# 4_Sensors.net
KiCad netlist of a schematic drawn in Altium Designer
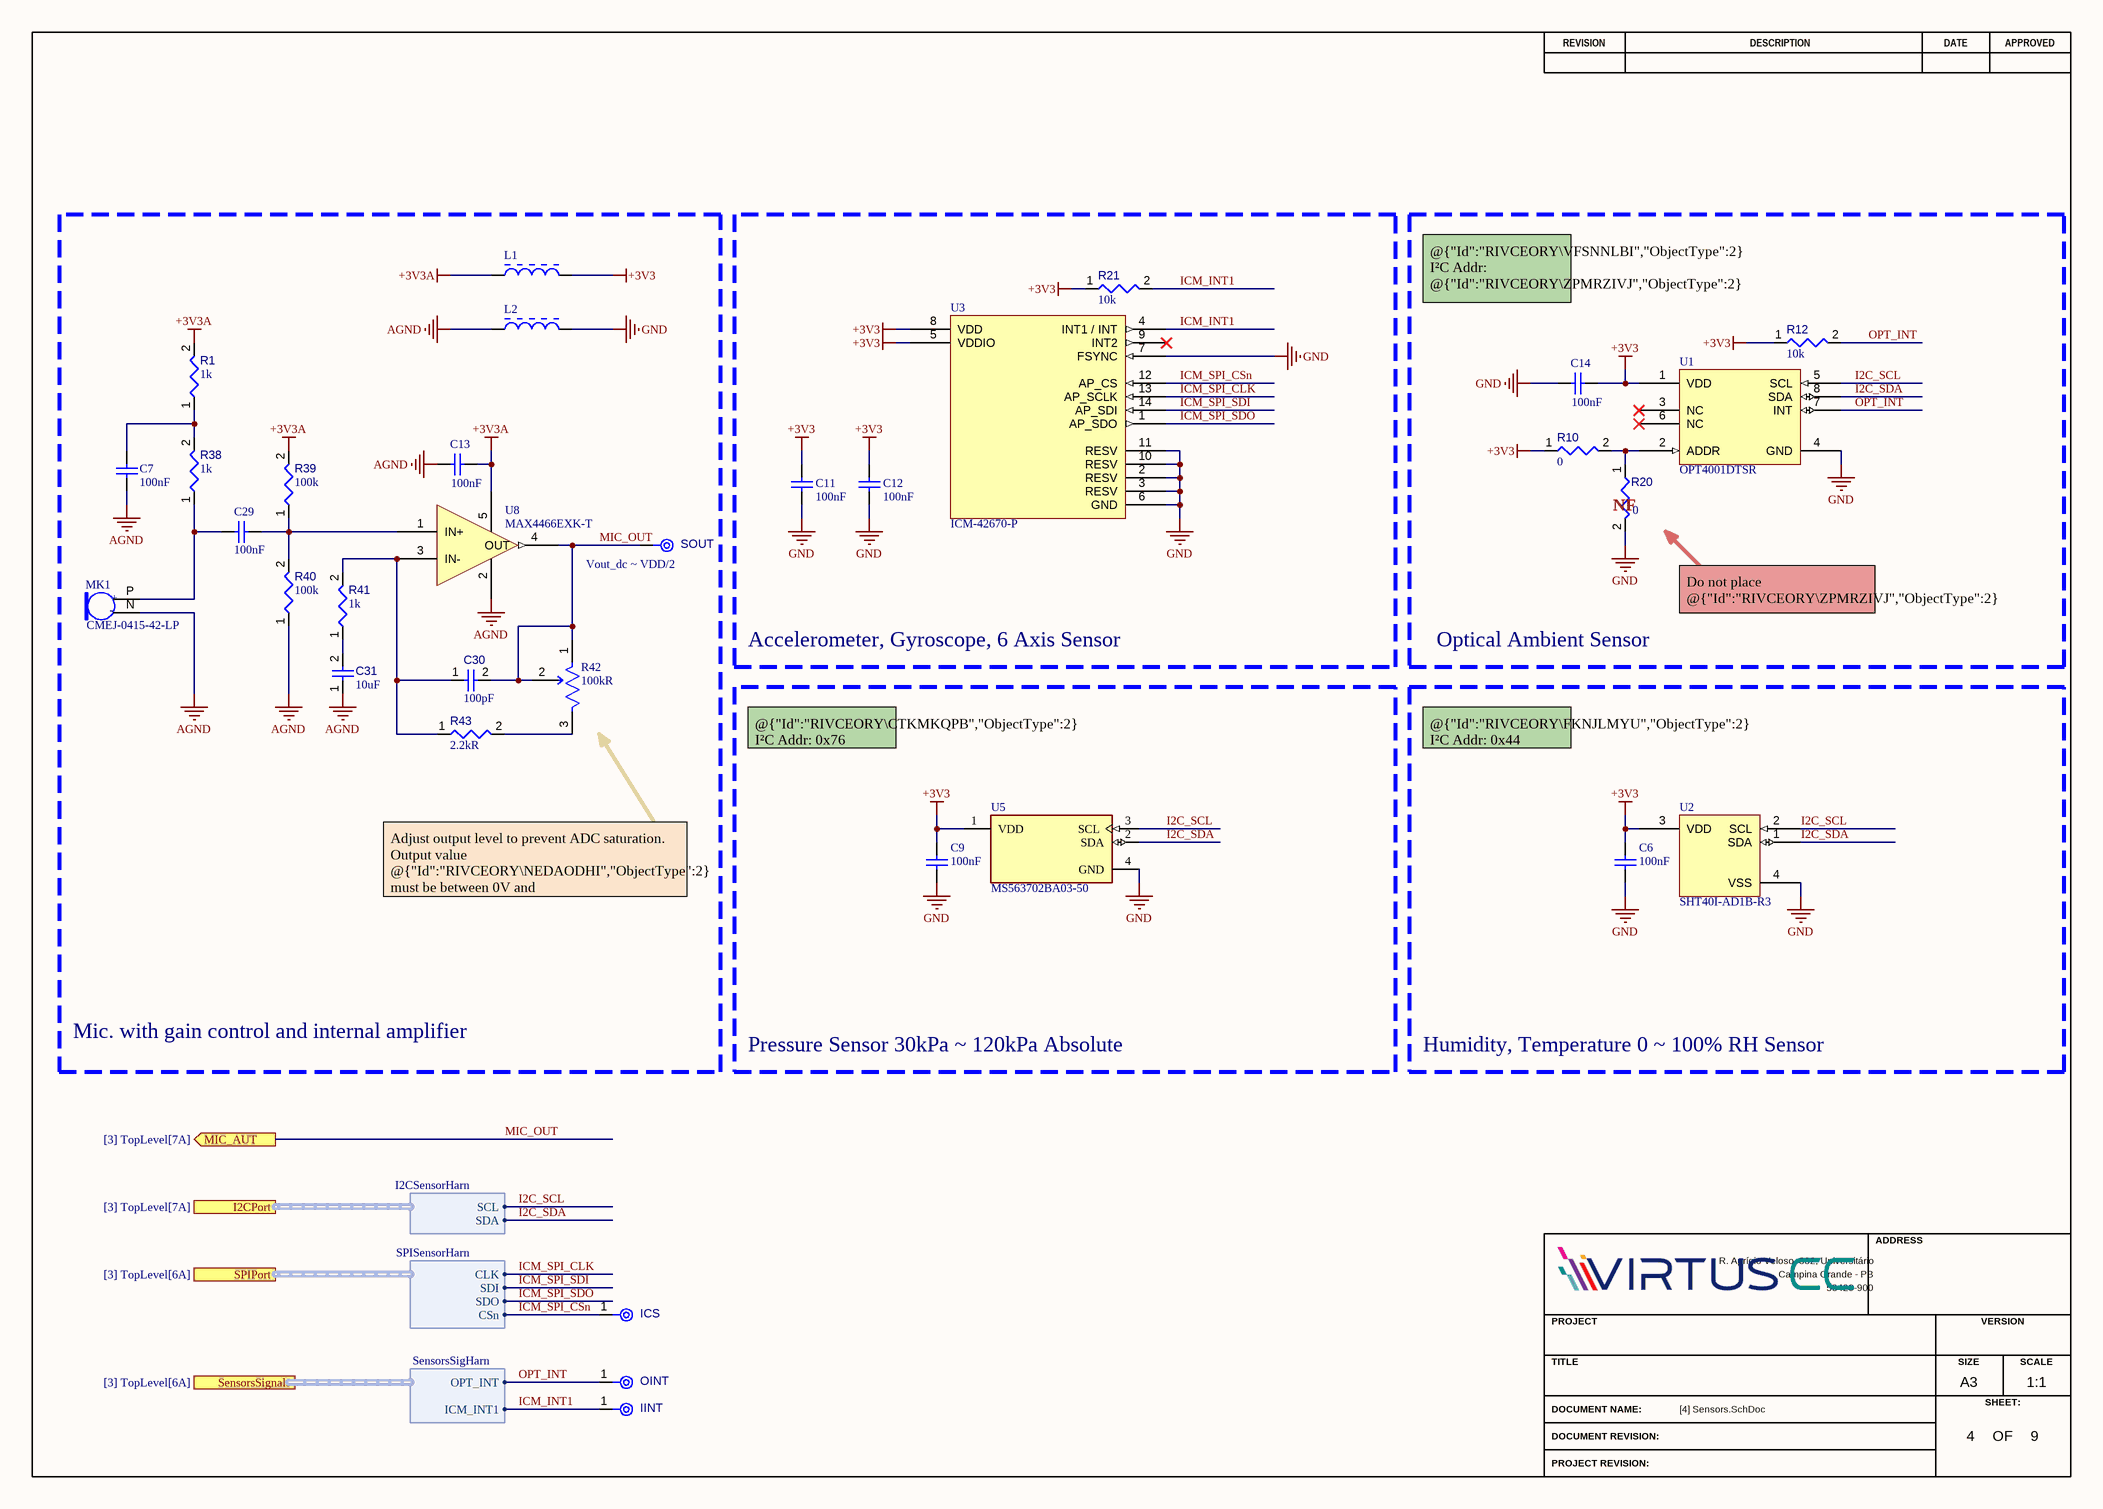
[diagram p0: [4] Sensors.SchDoc]

(export (version "E")
  (design (tool "Eeschema 10.0.6"))
  (components
    (comp (ref "C6")
      (value "100nF")
      (footprint "CAPC0603(1608)100_L")
      (description "Multilayer Ceramic Capacitor, 0.1 uF, 16 V, ± 20%, X7R, 0603 [1608 Metric]")
      (fields (field (name "TOLERANCE") "20%") (field (name "Comment") "VJ0603Y104MXJCW1BC"))
      (libsource (lib "UFCG - Universidade Federal de Campina Grande") (part "CAP"))
    )
    (comp (ref "C7")
      (value "100nF")
      (footprint "CAPC0603(1608)100_L")
      (description "Multilayer Ceramic Capacitor, 0.1 uF, 16 V, ± 20%, X7R, 0603 [1608 Metric]")
      (fields (field (name "TOLERANCE") "20%") (field (name "Comment") "VJ0603Y104MXJCW1BC"))
      (libsource (lib "UFCG - Universidade Federal de Campina Grande") (part "CAP"))
    )
    (comp (ref "C9")
      (value "100nF")
      (footprint "CAPC0603(1608)100_L")
      (description "Multilayer Ceramic Capacitor, 0.1 uF, 16 V, ± 20%, X7R, 0603 [1608 Metric]")
      (fields (field (name "TOLERANCE") "20%") (field (name "Comment") "VJ0603Y104MXJCW1BC"))
      (libsource (lib "UFCG - Universidade Federal de Campina Grande") (part "CAP"))
    )
    (comp (ref "C11")
      (value "100nF")
      (footprint "CAPC0603(1608)100_L")
      (description "Multilayer Ceramic Capacitor, 0.1 uF, 16 V, ± 20%, X7R, 0603 [1608 Metric]")
      (fields (field (name "TOLERANCE") "20%") (field (name "Comment") "VJ0603Y104MXJCW1BC"))
      (libsource (lib "UFCG - Universidade Federal de Campina Grande") (part "CAP"))
    )
    (comp (ref "C12")
      (value "100nF")
      (footprint "CAPC0603(1608)100_L")
      (description "Multilayer Ceramic Capacitor, 0.1 uF, 16 V, ± 20%, X7R, 0603 [1608 Metric]")
      (fields (field (name "TOLERANCE") "20%") (field (name "Comment") "VJ0603Y104MXJCW1BC"))
      (libsource (lib "UFCG - Universidade Federal de Campina Grande") (part "CAP"))
    )
    (comp (ref "C13")
      (value "100nF")
      (footprint "CAPC0603(1608)100_L")
      (description "Multilayer Ceramic Capacitor, 0.1 uF, 16 V, ± 20%, X7R, 0603 [1608 Metric]")
      (fields (field (name "TOLERANCE") "20%") (field (name "Comment") "VJ0603Y104MXJCW1BC"))
      (libsource (lib "UFCG - Universidade Federal de Campina Grande") (part "CAP"))
    )
    (comp (ref "C14")
      (value "100nF")
      (footprint "CAPC0603(1608)100_L")
      (description "Multilayer Ceramic Capacitor, 0.1 uF, 16 V, ± 20%, X7R, 0603 [1608 Metric]")
      (fields (field (name "TOLERANCE") "20%") (field (name "Comment") "VJ0603Y104MXJCW1BC"))
      (libsource (lib "UFCG - Universidade Federal de Campina Grande") (part "CAP"))
    )
    (comp (ref "C29")
      (value "100nF")
      (footprint "CAPC0603(1608)100_L")
      (description "Multilayer Ceramic Capacitor, 0.1 uF, 16 V, ± 20%, X7R, 0603 [1608 Metric]")
      (fields (field (name "TOLERANCE") "20%") (field (name "Comment") "VJ0603Y104MXJCW1BC"))
      (libsource (lib "UFCG - Universidade Federal de Campina Grande") (part "CAP"))
    )
    (comp (ref "C30")
      (value "100pF")
      (footprint "CAPC0603(1608)100_L")
      (description "Multilayer Ceramic Capacitor, 100 pF, 50 V, ï¿½ 10%, C0G (NP0), 0603 [1608 Metric]")
      (fields (field (name "TOLERANCE") "10%") (field (name "Comment") "C0603C101K5GACTU"))
      (libsource (lib "UFCG - Universidade Federal de Campina Grande") (part "CAP-NP-2"))
    )
    (comp (ref "C31")
      (value "10uF")
      (footprint "CAPC0603(1608)100_L")
      (description "Multilayer Ceramic Capacitor, 10 uF, 6.3 V, ± 20%, X5R, 0603 [1608 Metric]")
      (fields (field (name "TOLERANCE") "20%") (field (name "Comment") "GRM188R60J106ME47D"))
      (libsource (lib "UFCG - Universidade Federal de Campina Grande") (part "CAP-NP-2"))
    )
    (comp (ref "ICS")
      (value "TPAD6R")
      (footprint "TP06R")
      (description "0.6mm round")
      (libsource (lib "") (part "CMP-001-0001-4_1"))
    )
    (comp (ref "IINT")
      (value "TPAD6R")
      (footprint "TP06R")
      (description "0.6mm round")
      (libsource (lib "") (part "CMP-001-0001-4_1"))
    )
    (comp (ref "L1")
      (value "BLM21PG331SN1D")
      (footprint "INDC2013X105X50ML20T20")
      (fields (field (name "TOLERANCE") "25%") (field (name "MANUFACTURER") "Murata"))
      (libsource (lib "UFCG - Universidade Federal de Campina Grande") (part "IND-FB-2"))
    )
    (comp (ref "L2")
      (value "BLM21PG331SN1D")
      (footprint "INDC2013X105X50ML20T20")
      (fields (field (name "TOLERANCE") "25%") (field (name "MANUFACTURER") "Murata"))
      (libsource (lib "UFCG - Universidade Federal de Campina Grande") (part "IND-FB-2"))
    )
    (comp (ref "MK1")
      (value "CMEJ-0415-42-LP")
      (footprint "MIC_CMEJ-0415-42-LP")
      (description "4.0 mm, Omnidirectional, PCB Mount, 2.0 Vdc, Elecret Condenser Microphone")
      (fields (field (name "MF") "{'manufacturer': u'CUI'}"))
      (libsource (lib "UFCG - Universidade Federal de Campina Grande") (part "CMEJ-0415-42-LP"))
    )
    (comp (ref "OINT")
      (value "TPAD6R")
      (footprint "TP06R")
      (description "0.6mm round")
      (libsource (lib "") (part "CMP-001-0001-4_1"))
    )
    (comp (ref "R1")
      (value "1k")
      (footprint "RESC0603(1608)_L")
      (description "Chip Resistor, 1 KOhm, +/-1%, 0.1 W, -55 to 155 degC, 0603 (1608 Metric)")
      (fields (field (name "POWER") "100mW") (field (name "TOLERANCE") "1%"))
      (libsource (lib "UFCG - Universidade Federal de Campina Grande") (part "RES-2"))
    )
    (comp (ref "R10")
      (value "0")
      (footprint "RESC0603(1608)_L")
      (description "Chip Resistor, 0 Ohm, 0.1 W, -55 to 155 degC, 0603 (1608 Metric)")
      (fields (field (name "TOLERANCE") "5%") (field (name "POWER") "100mW"))
      (libsource (lib "UFCG - Universidade Federal de Campina Grande") (part "RES-2"))
    )
    (comp (ref "R12")
      (value "10k")
      (footprint "RESC0603(1608)_L")
      (description "Chip Resistor, 10 KOhm, +/- 1%, 01 W, -55 to 155 degC, 0603 (1608 Metric)")
      (fields (field (name "POWER") "100mW") (field (name "TOLERANCE") "1%"))
      (libsource (lib "UFCG - Universidade Federal de Campina Grande") (part "RES-2"))
    )
    (comp (ref "R20")
      (value "0")
      (footprint "RESC0603(1608)_L")
      (description "Chip Resistor, 0 Ohm, 0.1 W, -55 to 155 degC, 0603 (1608 Metric)")
      (fields (field (name "TOLERANCE") "5%") (field (name "POWER") "100mW"))
      (libsource (lib "UFCG - Universidade Federal de Campina Grande") (part "RES-2"))
    )
    (comp (ref "R21")
      (value "10k")
      (footprint "RESC0603(1608)_L")
      (description "Chip Resistor, 10 KOhm, +/- 1%, 01 W, -55 to 155 degC, 0603 (1608 Metric)")
      (fields (field (name "POWER") "100mW") (field (name "TOLERANCE") "1%"))
      (libsource (lib "UFCG - Universidade Federal de Campina Grande") (part "RES-2"))
    )
    (comp (ref "R38")
      (value "1k")
      (footprint "RESC0603(1608)_L")
      (description "Chip Resistor, 1 KOhm, +/-1%, 0.1 W, -55 to 155 degC, 0603 (1608 Metric)")
      (fields (field (name "POWER") "100mW") (field (name "TOLERANCE") "1%"))
      (libsource (lib "UFCG - Universidade Federal de Campina Grande") (part "RES-2"))
    )
    (comp (ref "R39")
      (value "100k")
      (footprint "RESC0603(1608)_L")
      (description "Chip Resistor, 100 KOhm, +/- 1%, 0.1 W, -55 to 155 degC, 0603 (1608 Metric)")
      (fields (field (name "TOLERANCE") "1%") (field (name "POWER") "100mW"))
      (libsource (lib "UFCG - Universidade Federal de Campina Grande") (part "RES-2"))
    )
    (comp (ref "R40")
      (value "100k")
      (footprint "RESC0603(1608)_L")
      (description "Chip Resistor, 100 KOhm, +/- 1%, 0.1 W, -55 to 155 degC, 0603 (1608 Metric)")
      (fields (field (name "TOLERANCE") "1%") (field (name "POWER") "100mW"))
      (libsource (lib "UFCG - Universidade Federal de Campina Grande") (part "RES-2"))
    )
    (comp (ref "R41")
      (value "1k")
      (footprint "RESC0603(1608)_L")
      (description "Chip Resistor, 1 KOhm, +/-1%, 0.1 W, -55 to 155 degC, 0603 (1608 Metric)")
      (fields (field (name "POWER") "100mW") (field (name "TOLERANCE") "1%"))
      (libsource (lib "UFCG - Universidade Federal de Campina Grande") (part "RES-2"))
    )
    (comp (ref "R42")
      (value "100kR")
      (footprint "FP-TC33X-2-MFG")
      (description "Cermet trimmer potentiometer, 100 kΩ, 0.1 W, SMD, on top, TC33X-2-104E")
      (fields (field (name "TOLERANCE") "25%") (field (name "Comment") "TC33X-2-104E"))
      (libsource (lib "UFCG - Universidade Federal de Campina Grande") (part "13357d81287629c2fd191d242cfa50c"))
    )
    (comp (ref "R43")
      (value "2.2kR")
      (footprint "RESC0603(1608)_L")
      (description "SMD Chip Resistor, 2.2 kOhm, ± 1%, 100 mW, 0603 [1608 Metric], Thick Film, General Purpose")
      (fields (field (name "TOLERANCE") "1%") (field (name "Comment") "CRCW06032K20FKEA"))
      (libsource (lib "UFCG - Universidade Federal de Campina Grande") (part "RES-2"))
    )
    (comp (ref "SOUT")
      (value "TPAD6R")
      (footprint "TP06R")
      (description "0.6mm round")
      (libsource (lib "UFCG - Universidade Federal de Campina Grande") (part "CMP-001-0001-4"))
    )
    (comp (ref "U1")
      (value "OPT4001DTSR")
      (footprint "SON50P130X60-8N")
      (description "High-speed high-precision digital ambient light sensor (ALS) 8-SOT-5X3 -40 to 85")
      (libsource (lib "UFCG - Universidade Federal de Campina Grande") (part "New symbol 1"))
    )
    (comp (ref "U2")
      (value "SHT40I-AD1B-R3")
      (footprint "QFN80P150X150X55-4N")
      (description "Humidity And Temperature Sensor")
      (libsource (lib "UFCG - Universidade Federal de Campina Grande") (part "SHT40I-AD1B-R3"))
    )
    (comp (ref "U3")
      (value "ICM-42670-P")
      (footprint "QFN50P300X250X81-14N")
      (description "Mems Module, 1.71-3.6 V, Lga-14 Rohs Compliant: Yes")
      (libsource (lib "UFCG - Universidade Federal de Campina Grande") (part "ICM-42670-P"))
    )
    (comp (ref "U5")
      (value "MS563702BA03-50")
      (footprint "FP-MS563702BA03-50-MFG")
      (description "Pressure Sensor, Barometric, 300 mbar, 1200 mbar, QFN, 8, -40 C")
      (libsource (lib "UFCG - Universidade Federal de Campina Grande") (part "74709a9a55dd6d6ee219151e6d8b12f"))
    )
    (comp (ref "U8")
      (value "MAX4466EXK-T")
      (footprint "SOT65P200X110-5N")
      (description "Audio Amp Microphone 1-CH Mono Class-AB 5-Pin SC-70 T/R")
      (libsource (lib "UFCG - Universidade Federal de Campina Grande") (part "MAX4466EXK-T"))
    )
  )
  (nets
    (net (code "4") (name "+3V3") (class "Default")
      (node (ref "C11") (pin "2") (pinfunction "2_2") (pintype "passive"))
      (node (ref "C12") (pin "2") (pinfunction "2_2") (pintype "passive"))
      (node (ref "C14") (pin "1") (pinfunction "1_1") (pintype "passive"))
      (node (ref "C6") (pin "1") (pinfunction "1_1") (pintype "passive"))
      (node (ref "C9") (pin "1") (pinfunction "1_1") (pintype "passive"))
      (node (ref "L1") (pin "2") (pinfunction "2_2") (pintype "passive"))
      (node (ref "R10") (pin "1") (pinfunction "1_1") (pintype "passive"))
      (node (ref "R12") (pin "1") (pinfunction "1_1") (pintype "passive"))
      (node (ref "R21") (pin "1") (pinfunction "1_1") (pintype "passive"))
      (node (ref "U1") (pin "1") (pinfunction "VDD_1") (pintype "power_in"))
      (node (ref "U2") (pin "3") (pinfunction "VDD_3") (pintype "power_in"))
      (node (ref "U3") (pin "5") (pinfunction "VDDIO_5") (pintype "power_in"))
      (node (ref "U3") (pin "8") (pinfunction "VDD_8") (pintype "power_in"))
      (node (ref "U5") (pin "1") (pinfunction "VDD_1") (pintype "power_in"))
    )
    (net (code "5") (name "+3V3A") (class "Default")
      (node (ref "C13") (pin "1") (pinfunction "1_1") (pintype "passive"))
      (node (ref "L1") (pin "1") (pinfunction "1_1") (pintype "passive"))
      (node (ref "R1") (pin "2") (pinfunction "2_2") (pintype "passive"))
      (node (ref "R39") (pin "2") (pinfunction "2_2") (pintype "passive"))
      (node (ref "U8") (pin "5") (pinfunction "VCC_5") (pintype "power_in"))
    )
    (net (code "6") (name "/I2C_SCL") (class "Default")
      (node (ref "U1") (pin "5") (pinfunction "SCL_5") (pintype "input"))
      (node (ref "U2") (pin "2") (pinfunction "SCL_2") (pintype "input"))
      (node (ref "U5") (pin "3") (pinfunction "SCL_3") (pintype "input"))
    )
    (net (code "7") (name "/I2C_SDA") (class "Default")
      (node (ref "U1") (pin "8") (pinfunction "SDA_8") (pintype "bidirectional"))
      (node (ref "U2") (pin "1") (pinfunction "SDA_1") (pintype "bidirectional"))
      (node (ref "U5") (pin "2") (pinfunction "SDA_2") (pintype "bidirectional"))
    )
    (net (code "8") (name "/ICM_INT1") (class "Default")
      (node (ref "IINT") (pin "1") (pinfunction "TP_1") (pintype "passive"))
      (node (ref "R21") (pin "2") (pinfunction "2_2") (pintype "passive"))
      (node (ref "U3") (pin "4") (pinfunction "INT1_/_INT_4") (pintype "output"))
    )
    (net (code "9") (name "/ICM_SPI_CLK") (class "Default")
      (node (ref "U3") (pin "13") (pinfunction "AP_SCLK_13") (pintype "input"))
    )
    (net (code "10") (name "/ICM_SPI_CSn") (class "Default")
      (node (ref "ICS") (pin "1") (pinfunction "TP_1") (pintype "passive"))
      (node (ref "U3") (pin "12") (pinfunction "AP_CS_12") (pintype "input"))
    )
    (net (code "11") (name "/ICM_SPI_SDI") (class "Default")
      (node (ref "U3") (pin "14") (pinfunction "AP_SDI_14") (pintype "input"))
    )
    (net (code "12") (name "/ICM_SPI_SDO") (class "Default")
      (node (ref "U3") (pin "1") (pinfunction "AP_SDO_1") (pintype "output"))
    )
    (net (code "13") (name "/MIC_OUT") (class "Default")
      (node (ref "C30") (pin "2") (pinfunction "2_2") (pintype "passive"))
      (node (ref "R42") (pin "1") (pinfunction "CCW_1") (pintype "passive"))
      (node (ref "R42") (pin "2") (pinfunction "WIPER_2") (pintype "passive"))
      (node (ref "SOUT") (pin "1") (pinfunction "TP_1") (pintype "passive"))
      (node (ref "U8") (pin "4") (pinfunction "OUT_4") (pintype "output"))
    )
    (net (code "14") (name "/OPT_INT") (class "Default")
      (node (ref "OINT") (pin "1") (pinfunction "TP_1") (pintype "passive"))
      (node (ref "R12") (pin "2") (pinfunction "2_2") (pintype "passive"))
      (node (ref "U1") (pin "7") (pinfunction "INT_7") (pintype "bidirectional"))
    )
    (net (code "18") (name "AGND") (class "Default")
      (node (ref "C13") (pin "2") (pinfunction "2_2") (pintype "passive"))
      (node (ref "C31") (pin "1") (pinfunction "1_1") (pintype "passive"))
      (node (ref "C7") (pin "1") (pinfunction "1_1") (pintype "passive"))
      (node (ref "L2") (pin "1") (pinfunction "1_1") (pintype "passive"))
      (node (ref "MK1") (pin "N") (pinfunction "GND_N") (pintype "passive"))
      (node (ref "R40") (pin "1") (pinfunction "1_1") (pintype "passive"))
      (node (ref "U8") (pin "2") (pinfunction "GND_2") (pintype "power_in"))
    )
    (net (code "19") (name "GND") (class "Default")
      (node (ref "C11") (pin "1") (pinfunction "1_1") (pintype "passive"))
      (node (ref "C12") (pin "1") (pinfunction "1_1") (pintype "passive"))
      (node (ref "C14") (pin "2") (pinfunction "2_2") (pintype "passive"))
      (node (ref "C6") (pin "2") (pinfunction "2_2") (pintype "passive"))
      (node (ref "C9") (pin "2") (pinfunction "2_2") (pintype "passive"))
      (node (ref "L2") (pin "2") (pinfunction "2_2") (pintype "passive"))
      (node (ref "R20") (pin "2") (pinfunction "2_2") (pintype "passive"))
      (node (ref "U1") (pin "4") (pinfunction "GND_4") (pintype "power_in"))
      (node (ref "U2") (pin "4") (pinfunction "VSS_4") (pintype "power_in"))
      (node (ref "U3") (pin "10") (pinfunction "RESV_10") (pintype "passive"))
      (node (ref "U3") (pin "11") (pinfunction "RESV_11") (pintype "passive"))
      (node (ref "U3") (pin "2") (pinfunction "RESV_2") (pintype "passive"))
      (node (ref "U3") (pin "3") (pinfunction "RESV_3") (pintype "passive"))
      (node (ref "U3") (pin "6") (pinfunction "GND_6") (pintype "power_in"))
      (node (ref "U3") (pin "7") (pinfunction "FSYNC_7") (pintype "input"))
      (node (ref "U5") (pin "4") (pinfunction "GND_4") (pintype "power_in"))
    )
    (net (code "20") (name "Net-(C7-Pad2)") (class "Default")
      (node (ref "C7") (pin "2") (pinfunction "2_2") (pintype "passive"))
      (node (ref "R1") (pin "1") (pinfunction "1_1") (pintype "passive"))
      (node (ref "R38") (pin "2") (pinfunction "2_2") (pintype "passive"))
    )
    (net (code "21") (name "Net-(C31-Pad2)") (class "Default")
      (node (ref "C31") (pin "2") (pinfunction "2_2") (pintype "passive"))
      (node (ref "R41") (pin "1") (pinfunction "1_1") (pintype "passive"))
    )
    (net (code "22") (name "Net-(MK1-OUTPUT)") (class "Default")
      (node (ref "C29") (pin "2") (pinfunction "2_2") (pintype "passive"))
      (node (ref "MK1") (pin "P") (pinfunction "OUTPUT_P") (pintype "passive"))
      (node (ref "R38") (pin "1") (pinfunction "1_1") (pintype "passive"))
    )
    (net (code "23") (name "Net-(R42-CW)") (class "Default")
      (node (ref "R42") (pin "3") (pinfunction "CW_3") (pintype "passive"))
      (node (ref "R43") (pin "2") (pinfunction "2_2") (pintype "passive"))
    )
    (net (code "24") (name "Net-(U1-ADDR)") (class "Default")
      (node (ref "R10") (pin "2") (pinfunction "2_2") (pintype "passive"))
      (node (ref "R20") (pin "1") (pinfunction "1_1") (pintype "passive"))
      (node (ref "U1") (pin "2") (pinfunction "ADDR_2") (pintype "input"))
    )
    (net (code "25") (name "Net-(U8-IN+)") (class "Default")
      (node (ref "C29") (pin "1") (pinfunction "1_1") (pintype "passive"))
      (node (ref "R39") (pin "1") (pinfunction "1_1") (pintype "passive"))
      (node (ref "R40") (pin "2") (pinfunction "2_2") (pintype "passive"))
      (node (ref "U8") (pin "1") (pinfunction "IN+_1") (pintype "passive"))
    )
    (net (code "26") (name "Net-(U8-IN-)") (class "Default")
      (node (ref "C30") (pin "1") (pinfunction "1_1") (pintype "passive"))
      (node (ref "R41") (pin "2") (pinfunction "2_2") (pintype "passive"))
      (node (ref "R43") (pin "1") (pinfunction "1_1") (pintype "passive"))
      (node (ref "U8") (pin "3") (pinfunction "IN-_3") (pintype "passive"))
    )
    (net (code "27") (name "unconnected-(U1-NC-Pad3)") (class "Default")
      (node (ref "U1") (pin "3") (pinfunction "NC_3") (pintype "passive+no_connect"))
    )
    (net (code "28") (name "unconnected-(U1-NC-Pad6)") (class "Default")
      (node (ref "U1") (pin "6") (pinfunction "NC_6") (pintype "passive+no_connect"))
    )
    (net (code "29") (name "unconnected-(U3-INT2-Pad9)") (class "Default")
      (node (ref "U3") (pin "9") (pinfunction "INT2_9") (pintype "output+no_connect"))
    )
  )
)
